# magnet_driver.net
KiCad netlist of a schematic drawn in EAGLE
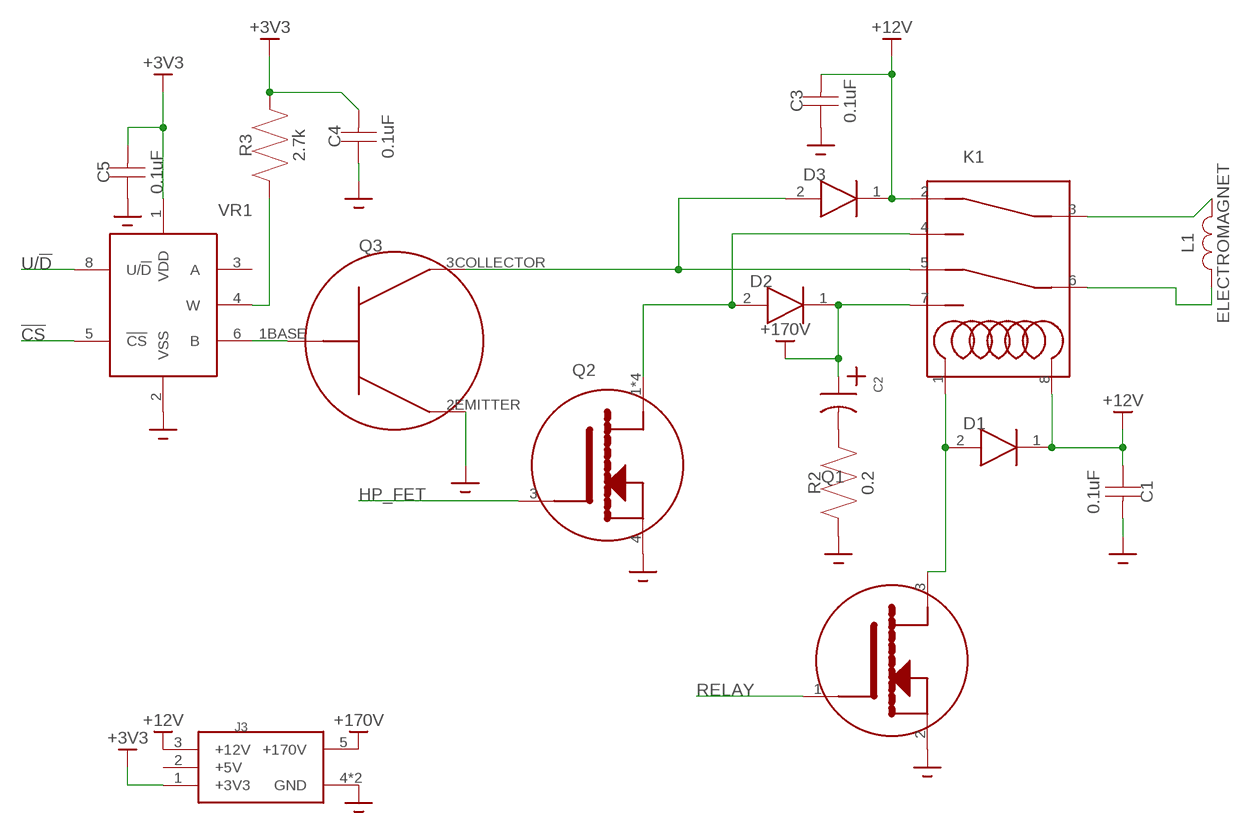
[diagram p0: schematic, sheet 1]
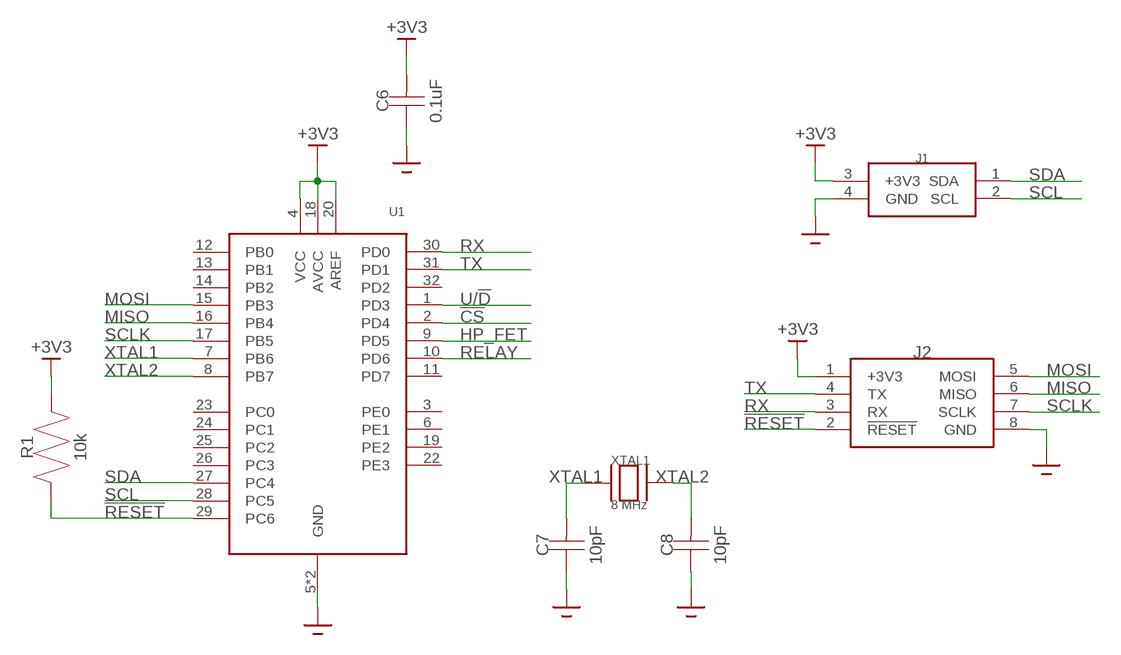
[diagram p1: schematic, sheet 2]

(export (version "E")
  (design (tool "Eeschema 10.0.6"))
  (components
    (comp (ref "C1")
      (value "0.1uF")
      (footprint "eagle-import:0805")
      (libsource (lib "eagle-import") (part "CAPACITOR0805"))
    )
    (comp (ref "C2")
      (value "ESMQ351VSN102MA50S")
      (footprint "eagle-import:ESMQ351VSN102MA50S")
      (libsource (lib "eagle-import") (part "ESMQ351VSN102MA50S"))
    )
    (comp (ref "C3")
      (value "0.1uF")
      (footprint "eagle-import:0805")
      (libsource (lib "eagle-import") (part "CAPACITOR0805"))
    )
    (comp (ref "C4")
      (value "0.1uF")
      (footprint "eagle-import:0805")
      (libsource (lib "eagle-import") (part "CAPACITOR0805"))
    )
    (comp (ref "C5")
      (value "0.1uF")
      (footprint "eagle-import:0805")
      (libsource (lib "eagle-import") (part "CAPACITOR0805"))
    )
    (comp (ref "D1")
      (value "BAT54HT1GBAT54HT1G")
      (footprint "eagle-import:SOD2512X110N")
      (libsource (lib "eagle-import") (part "BAT54HT1GBAT54HT1G"))
    )
    (comp (ref "D2")
      (value "BAT54HT1GBAT54HT1G")
      (footprint "eagle-import:SOD2512X110N")
      (libsource (lib "eagle-import") (part "BAT54HT1GBAT54HT1G"))
    )
    (comp (ref "D3")
      (value "BAT54HT1GBAT54HT1G")
      (footprint "eagle-import:SOD2512X110N")
      (libsource (lib "eagle-import") (part "BAT54HT1GBAT54HT1G"))
    )
    (comp (ref "J3")
      (value "1-770969-0")
      (footprint "eagle-import:1-770969-0")
      (libsource (lib "eagle-import") (part "1-770969-0"))
    )
    (comp (ref "K1")
      (value "G2RL-2DC12")
      (footprint "eagle-import:G2RL-2DC12")
      (libsource (lib "eagle-import") (part "G2RL-2DC12"))
    )
    (comp (ref "L1")
      (value "ELECTROMAGNET")
      (footprint "eagle-import:ELECTROMAGNET")
      (libsource (lib "eagle-import") (part "ELECTROMAGNET"))
    )
    (comp (ref "Q1")
      (value "RK7002BMT116")
      (footprint "eagle-import:SOT95P240X120-3N")
      (libsource (lib "eagle-import") (part "RK7002BMT116"))
    )
    (comp (ref "Q2")
      (value "DMN1019UVT-7DMN1019UVT-7")
      (footprint "eagle-import:SOT95P280X100-6N")
      (libsource (lib "eagle-import") (part "DMN1019UVT-7DMN1019UVT-7"))
    )
    (comp (ref "Q3")
      (value "PMBT2222A,215PMBT2222A,215")
      (footprint "eagle-import:SOT95P230X110-3N")
      (libsource (lib "eagle-import") (part "PMBT2222A,215PMBT2222A,215"))
    )
    (comp (ref "R2")
      (value "0.2")
      (footprint "eagle-import:0805")
      (libsource (lib "eagle-import") (part "RESISTOR0805"))
    )
    (comp (ref "R3")
      (value "2.7k")
      (footprint "eagle-import:0805")
      (libsource (lib "eagle-import") (part "RESISTOR0805"))
    )
    (comp (ref "VR1")
      (value "MCP4011-103E/MSMCP4011-103E/MS")
      (footprint "eagle-import:SOP65P490X265-8N")
      (libsource (lib "eagle-import") (part "MCP4011-103E/MSMCP4011-103E/MS"))
    )
    (comp (ref "C6")
      (value "0.1uF")
      (footprint "eagle-import:0805")
      (libsource (lib "eagle-import") (part "CAPACITOR0805"))
    )
    (comp (ref "C7")
      (value "10pF")
      (footprint "eagle-import:0805")
      (libsource (lib "eagle-import") (part "CAPACITOR0805"))
    )
    (comp (ref "C8")
      (value "10pF")
      (footprint "eagle-import:0805")
      (libsource (lib "eagle-import") (part "CAPACITOR0805"))
    )
    (comp (ref "J1")
      (value "1-770968-0")
      (footprint "eagle-import:1-770968-0")
      (libsource (lib "eagle-import") (part "1-770968-0"))
    )
    (comp (ref "J2")
      (value "DF1BZ-8DP-2.5DSA")
      (footprint "eagle-import:DF1BZ-8DP-2.5DSA")
      (libsource (lib "eagle-import") (part "DF1BZ-8DP-2.5DSA"))
    )
    (comp (ref "R1")
      (value "10k")
      (footprint "eagle-import:0805")
      (libsource (lib "eagle-import") (part "RESISTOR0805"))
    )
    (comp (ref "U1")
      (value "ATMEGA328PB32-TQFP")
      (footprint "eagle-import:ATMEGA328PB")
      (libsource (lib "eagle-import") (part "ATMEGA328PB32-TQFP"))
    )
    (comp (ref "XTAL1")
      (value "8 MHz")
      (footprint "eagle-import:XRCGB")
      (libsource (lib "eagle-import") (part "XRCGB"))
    )
  )
  (nets
    (net (code "1") (name "+3V3") (class "Default")
      (node (ref "C4") (pin "P$2") (pinfunction "P$2_P$2") (pintype "passive"))
      (node (ref "C5") (pin "P$2") (pinfunction "P$2_P$2") (pintype "passive"))
      (node (ref "C6") (pin "P$2") (pinfunction "P$2_P$2") (pintype "passive"))
      (node (ref "J1") (pin "3") (pinfunction "+3V3_3") (pintype "power_in"))
      (node (ref "J2") (pin "1") (pinfunction "+3V3_1") (pintype "power_in"))
      (node (ref "J3") (pin "1") (pinfunction "+3V3_1") (pintype "power_in"))
      (node (ref "R1") (pin "P$2") (pinfunction "P$2_P$2") (pintype "passive"))
      (node (ref "R3") (pin "P$2") (pinfunction "P$2_P$2") (pintype "passive"))
      (node (ref "U1") (pin "18") (pinfunction "AVCC_18") (pintype "power_in"))
      (node (ref "U1") (pin "20") (pinfunction "AREF_20") (pintype "power_in"))
      (node (ref "U1") (pin "4") (pinfunction "VCC_4") (pintype "power_in"))
      (node (ref "VR1") (pin "1") (pinfunction "VDD_1") (pintype "bidirectional"))
    )
    (net (code "2") (name "+5V") (class "Default")
      (node (ref "J3") (pin "2") (pinfunction "+5V_2") (pintype "power_in"))
    )
    (net (code "3") (name "+12V") (class "Default")
      (node (ref "C1") (pin "P$1") (pinfunction "P$1_P$1") (pintype "passive"))
      (node (ref "C3") (pin "P$2") (pinfunction "P$2_P$2") (pintype "passive"))
      (node (ref "D1") (pin "1") (pinfunction "CATHODE(1)_1") (pintype "bidirectional"))
      (node (ref "D3") (pin "1") (pinfunction "CATHODE(1)_1") (pintype "bidirectional"))
      (node (ref "J3") (pin "3") (pinfunction "+12V_3") (pintype "power_in"))
      (node (ref "K1") (pin "2") (pinfunction "A1_2") (pintype "bidirectional"))
      (node (ref "K1") (pin "8") (pinfunction "COILOUT_8") (pintype "bidirectional"))
    )
    (net (code "4") (name "+170V") (class "Default")
      (node (ref "C2") (pin "+") (pinfunction "+_+") (pintype "passive"))
      (node (ref "D2") (pin "1") (pinfunction "CATHODE(1)_1") (pintype "bidirectional"))
      (node (ref "J3") (pin "5") (pinfunction "+170V_5") (pintype "power_in"))
      (node (ref "K1") (pin "7") (pinfunction "B2_7") (pintype "bidirectional"))
    )
    (net (code "5") (name "GND") (class "Default")
      (node (ref "C1") (pin "P$2") (pinfunction "P$2_P$2") (pintype "passive"))
      (node (ref "C3") (pin "P$1") (pinfunction "P$1_P$1") (pintype "passive"))
      (node (ref "C4") (pin "P$1") (pinfunction "P$1_P$1") (pintype "passive"))
      (node (ref "C5") (pin "P$1") (pinfunction "P$1_P$1") (pintype "passive"))
      (node (ref "C6") (pin "P$1") (pinfunction "P$1_P$1") (pintype "passive"))
      (node (ref "C7") (pin "P$1") (pinfunction "P$1_P$1") (pintype "passive"))
      (node (ref "C8") (pin "P$1") (pinfunction "P$1_P$1") (pintype "passive"))
      (node (ref "J1") (pin "4") (pinfunction "GND_4") (pintype "passive"))
      (node (ref "J2") (pin "8") (pinfunction "GND_8") (pintype "passive"))
      (node (ref "J3") (pin "4") (pinfunction "GND_4") (pintype "passive"))
      (node (ref "J3") (pin "6") (pinfunction "GND_6") (pintype "passive"))
      (node (ref "Q1") (pin "2") (pinfunction "SOURCE(2)_2") (pintype "bidirectional"))
      (node (ref "Q2") (pin "4") (pinfunction "SOURCE(2)_4") (pintype "bidirectional"))
      (node (ref "Q3") (pin "2EMITTER") (pinfunction "2E_2EMITTER") (pintype "bidirectional"))
      (node (ref "R2") (pin "P$1") (pinfunction "P$1_P$1") (pintype "passive"))
      (node (ref "U1") (pin "21") (pinfunction "GND_21") (pintype "passive"))
      (node (ref "U1") (pin "5") (pinfunction "GND_5") (pintype "passive"))
      (node (ref "VR1") (pin "2") (pinfunction "VSS_2") (pintype "bidirectional"))
    )
    (net (code "6") (name "HP_FET") (class "Default")
      (node (ref "Q2") (pin "3") (pinfunction "GATE(1)_3") (pintype "bidirectional"))
      (node (ref "U1") (pin "9") (pinfunction "PD5_9") (pintype "bidirectional"))
    )
    (net (code "7") (name "MISO") (class "Default")
      (node (ref "J2") (pin "6") (pinfunction "MISO_6") (pintype "input"))
      (node (ref "U1") (pin "16") (pinfunction "PB4_16") (pintype "bidirectional"))
    )
    (net (code "8") (name "MOSI") (class "Default")
      (node (ref "J2") (pin "5") (pinfunction "MOSI_5") (pintype "output"))
      (node (ref "U1") (pin "15") (pinfunction "PB3_15") (pintype "bidirectional"))
    )
    (net (code "9") (name "Net-(C2-Pad-)") (class "Default")
      (node (ref "C2") (pin "-") (pinfunction "-_-") (pintype "passive"))
      (node (ref "R2") (pin "P$2") (pinfunction "P$2_P$2") (pintype "passive"))
    )
    (net (code "10") (name "Net-(D1-ANODE(2))") (class "Default")
      (node (ref "D1") (pin "2") (pinfunction "ANODE(2)_2") (pintype "bidirectional"))
      (node (ref "K1") (pin "1") (pinfunction "COILIN_1") (pintype "bidirectional"))
      (node (ref "Q1") (pin "3") (pinfunction "DRAIN(3)_3") (pintype "bidirectional"))
    )
    (net (code "11") (name "Net-(D2-ANODE(2))") (class "Default")
      (node (ref "D2") (pin "2") (pinfunction "ANODE(2)_2") (pintype "bidirectional"))
      (node (ref "K1") (pin "4") (pinfunction "A2_4") (pintype "bidirectional"))
      (node (ref "Q2") (pin "1") (pinfunction "DRAIN(3)_1") (pintype "bidirectional"))
      (node (ref "Q2") (pin "2") (pinfunction "DRAIN(3)_2") (pintype "bidirectional"))
      (node (ref "Q2") (pin "5") (pinfunction "DRAIN(3)_5") (pintype "bidirectional"))
      (node (ref "Q2") (pin "6") (pinfunction "DRAIN(3)_6") (pintype "bidirectional"))
    )
    (net (code "12") (name "Net-(D3-ANODE(2))") (class "Default")
      (node (ref "D3") (pin "2") (pinfunction "ANODE(2)_2") (pintype "bidirectional"))
      (node (ref "K1") (pin "5") (pinfunction "B1_5") (pintype "bidirectional"))
      (node (ref "Q3") (pin "3COLLECTOR") (pinfunction "3C_3COLLECTOR") (pintype "bidirectional"))
    )
    (net (code "13") (name "Net-(K1-A)") (class "Default")
      (node (ref "K1") (pin "3") (pinfunction "A_3") (pintype "bidirectional"))
      (node (ref "L1") (pin "-") (pinfunction "P$2_-") (pintype "passive"))
    )
    (net (code "14") (name "Net-(K1-B)") (class "Default")
      (node (ref "K1") (pin "6") (pinfunction "B_6") (pintype "bidirectional"))
      (node (ref "L1") (pin "+") (pinfunction "P$1_+") (pintype "passive"))
    )
    (net (code "15") (name "Net-(Q3-1B)") (class "Default")
      (node (ref "Q3") (pin "1BASE") (pinfunction "1B_1BASE") (pintype "bidirectional"))
      (node (ref "VR1") (pin "6") (pinfunction "B_6") (pintype "bidirectional"))
    )
    (net (code "16") (name "Net-(VR1-W)") (class "Default")
      (node (ref "R3") (pin "P$1") (pinfunction "P$1_P$1") (pintype "passive"))
      (node (ref "VR1") (pin "4") (pinfunction "W_4") (pintype "bidirectional"))
    )
    (net (code "17") (name "RELAY") (class "Default")
      (node (ref "Q1") (pin "1") (pinfunction "GATE(1)_1") (pintype "bidirectional"))
      (node (ref "U1") (pin "10") (pinfunction "PD6_10") (pintype "bidirectional"))
    )
    (net (code "18") (name "RX") (class "Default")
      (node (ref "J2") (pin "3") (pinfunction "RX_3") (pintype "output"))
      (node (ref "U1") (pin "30") (pinfunction "PD0_30") (pintype "bidirectional"))
    )
    (net (code "19") (name "SCL") (class "Default")
      (node (ref "J1") (pin "2") (pinfunction "SCL_2") (pintype "bidirectional"))
      (node (ref "U1") (pin "28") (pinfunction "PC5_28") (pintype "bidirectional"))
    )
    (net (code "20") (name "SCLK") (class "Default")
      (node (ref "J2") (pin "7") (pinfunction "SCLK_7") (pintype "output"))
      (node (ref "U1") (pin "17") (pinfunction "PB5_17") (pintype "bidirectional"))
    )
    (net (code "21") (name "SDA") (class "Default")
      (node (ref "J1") (pin "1") (pinfunction "SDA_1") (pintype "bidirectional"))
      (node (ref "U1") (pin "27") (pinfunction "PC4_27") (pintype "bidirectional"))
    )
    (net (code "22") (name "TX") (class "Default")
      (node (ref "J2") (pin "4") (pinfunction "TX_4") (pintype "input"))
      (node (ref "U1") (pin "31") (pinfunction "PD1_31") (pintype "bidirectional"))
    )
    (net (code "23") (name "U{slash}~{D}") (class "Default")
      (node (ref "U1") (pin "1") (pinfunction "PD3_1") (pintype "bidirectional"))
      (node (ref "VR1") (pin "8") (pinfunction "U/~{D}_8") (pintype "bidirectional"))
    )
    (net (code "24") (name "XTAL1") (class "Default")
      (node (ref "C7") (pin "P$2") (pinfunction "P$2_P$2") (pintype "passive"))
      (node (ref "U1") (pin "7") (pinfunction "PB6_7") (pintype "bidirectional"))
      (node (ref "XTAL1") (pin "1") (pinfunction "P$1_1") (pintype "passive"))
      (node (ref "XTAL1") (pin "3") (pinfunction "P$1_3") (pintype "passive"))
    )
    (net (code "25") (name "XTAL2") (class "Default")
      (node (ref "C8") (pin "P$2") (pinfunction "P$2_P$2") (pintype "passive"))
      (node (ref "U1") (pin "8") (pinfunction "PB7_8") (pintype "bidirectional"))
      (node (ref "XTAL1") (pin "2") (pinfunction "P$2_2") (pintype "passive"))
      (node (ref "XTAL1") (pin "4") (pinfunction "P$2_4") (pintype "passive"))
    )
    (net (code "26") (name "unconnected-(U1-PB0-Pad12)") (class "Default")
      (node (ref "U1") (pin "12") (pinfunction "PB0_12") (pintype "bidirectional"))
    )
    (net (code "27") (name "unconnected-(U1-PB1-Pad13)") (class "Default")
      (node (ref "U1") (pin "13") (pinfunction "PB1_13") (pintype "bidirectional"))
    )
    (net (code "28") (name "unconnected-(U1-PB2-Pad14)") (class "Default")
      (node (ref "U1") (pin "14") (pinfunction "PB2_14") (pintype "bidirectional"))
    )
    (net (code "29") (name "unconnected-(U1-PC0-Pad23)") (class "Default")
      (node (ref "U1") (pin "23") (pinfunction "PC0_23") (pintype "bidirectional"))
    )
    (net (code "30") (name "unconnected-(U1-PC1-Pad24)") (class "Default")
      (node (ref "U1") (pin "24") (pinfunction "PC1_24") (pintype "bidirectional"))
    )
    (net (code "31") (name "unconnected-(U1-PC2-Pad25)") (class "Default")
      (node (ref "U1") (pin "25") (pinfunction "PC2_25") (pintype "bidirectional"))
    )
    (net (code "32") (name "unconnected-(U1-PC3-Pad26)") (class "Default")
      (node (ref "U1") (pin "26") (pinfunction "PC3_26") (pintype "bidirectional"))
    )
    (net (code "33") (name "unconnected-(U1-PD2-Pad32)") (class "Default")
      (node (ref "U1") (pin "32") (pinfunction "PD2_32") (pintype "bidirectional"))
    )
    (net (code "34") (name "unconnected-(U1-PD7-Pad11)") (class "Default")
      (node (ref "U1") (pin "11") (pinfunction "PD7_11") (pintype "bidirectional"))
    )
    (net (code "35") (name "unconnected-(U1-PE0-Pad3)") (class "Default")
      (node (ref "U1") (pin "3") (pinfunction "PE0_3") (pintype "bidirectional"))
    )
    (net (code "36") (name "unconnected-(U1-PE1-Pad6)") (class "Default")
      (node (ref "U1") (pin "6") (pinfunction "PE1_6") (pintype "bidirectional"))
    )
    (net (code "37") (name "unconnected-(U1-PE2-Pad19)") (class "Default")
      (node (ref "U1") (pin "19") (pinfunction "PE2_19") (pintype "bidirectional"))
    )
    (net (code "38") (name "unconnected-(U1-PE3-Pad22)") (class "Default")
      (node (ref "U1") (pin "22") (pinfunction "PE3_22") (pintype "bidirectional"))
    )
    (net (code "39") (name "unconnected-(VR1-A-Pad3)") (class "Default")
      (node (ref "VR1") (pin "3") (pinfunction "A_3") (pintype "bidirectional"))
    )
    (net (code "40") (name "~{CS}") (class "Default")
      (node (ref "U1") (pin "2") (pinfunction "PD4_2") (pintype "bidirectional"))
      (node (ref "VR1") (pin "5") (pinfunction "~{CS}_5") (pintype "bidirectional"))
    )
    (net (code "41") (name "~{RESET}") (class "Default")
      (node (ref "J2") (pin "2") (pinfunction "~{RESET}_2") (pintype "output"))
      (node (ref "R1") (pin "P$1") (pinfunction "P$1_P$1") (pintype "passive"))
      (node (ref "U1") (pin "29") (pinfunction "PC6_29") (pintype "bidirectional"))
    )
  )
)
